# gps_transmitter_featherwing_v1_0.net
KiCad netlist of a schematic drawn in EAGLE
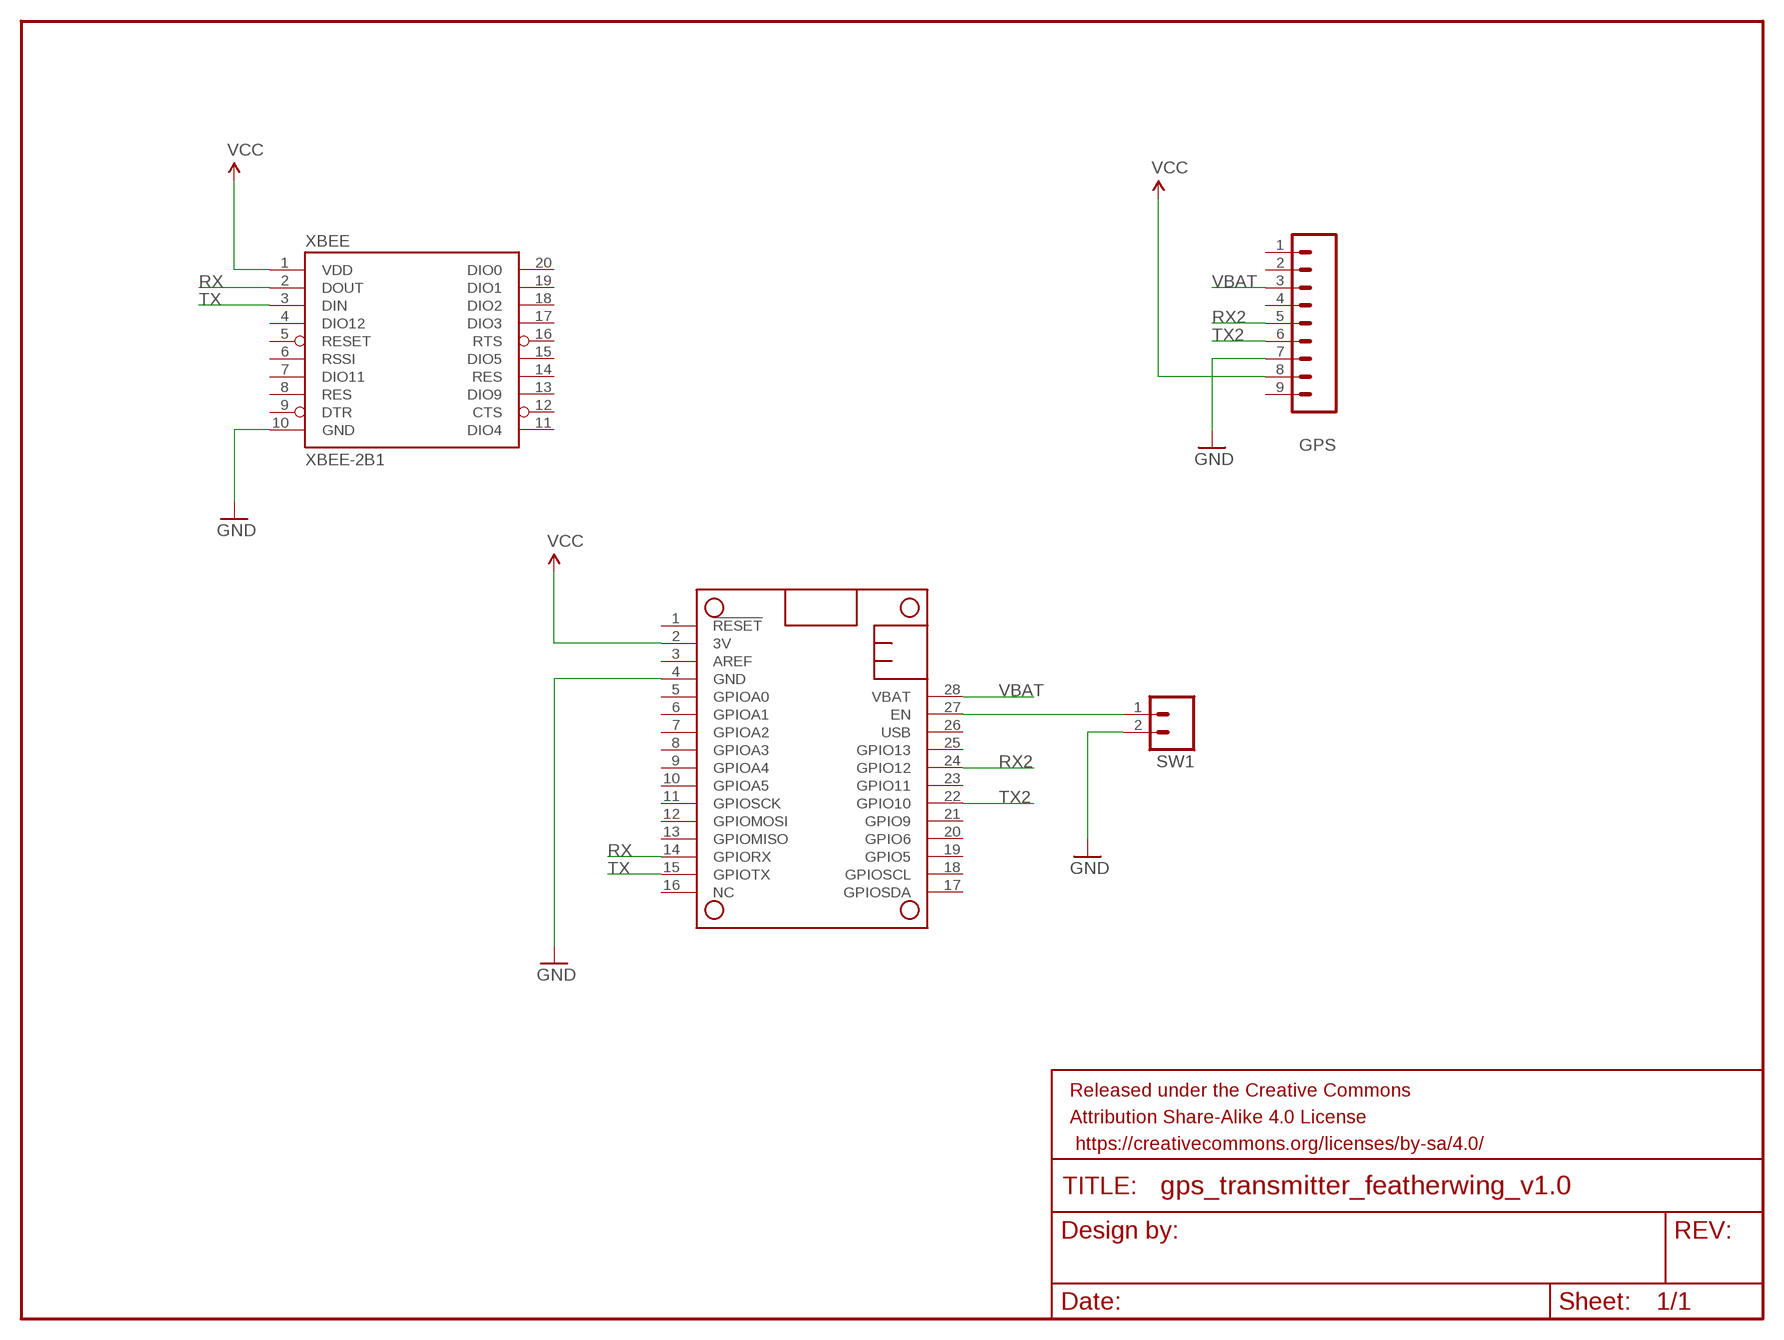
[diagram p0: schematic, sheet 1]

(export (version "E")
  (design (tool "Eeschema 10.0.6"))
  (components
    (comp (ref "FRAME1")
      (value "FRAME-LETTER")
      (footprint "eagle-import:CREATIVE_COMMONS")
      (libsource (lib "eagle-import") (part "FRAME-LETTER"))
    )
    (comp (ref "GPS")
      (value "M09")
      (footprint "eagle-import:1X09")
      (libsource (lib "eagle-import") (part "M09"))
    )
    (comp (ref "MS1")
      (value "FEATHERWING_NODIM")
      (footprint "eagle-import:FEATHERWING_DIM")
      (libsource (lib "eagle-import") (part "FEATHERWING_NODIM"))
    )
    (comp (ref "SW1")
      (value "M023.5MM")
      (footprint "eagle-import:SCREWTERMINAL-3.5MM-2")
      (libsource (lib "eagle-import") (part "M023.5MM"))
    )
    (comp (ref "XBEE")
      (value "XBEE-2B1")
      (footprint "eagle-import:XBEE-1")
      (libsource (lib "eagle-import") (part "XBEE-2B1"))
    )
  )
  (nets
    (net (code "1") (name "/RX") (class "Default")
      (node (ref "MS1") (pin "14") (pinfunction "GPIORX_14") (pintype "bidirectional"))
      (node (ref "XBEE") (pin "2") (pinfunction "DOUT_2") (pintype "output"))
    )
    (net (code "2") (name "/RX2") (class "Default")
      (node (ref "GPS") (pin "5") (pinfunction "5_5") (pintype "passive"))
      (node (ref "MS1") (pin "24") (pinfunction "GPIO12_24") (pintype "bidirectional"))
    )
    (net (code "3") (name "/TX") (class "Default")
      (node (ref "MS1") (pin "15") (pinfunction "GPIOTX_15") (pintype "bidirectional"))
      (node (ref "XBEE") (pin "3") (pinfunction "DIN_3") (pintype "input"))
    )
    (net (code "4") (name "/TX2") (class "Default")
      (node (ref "GPS") (pin "6") (pinfunction "6_6") (pintype "passive"))
      (node (ref "MS1") (pin "22") (pinfunction "GPIO10_22") (pintype "bidirectional"))
    )
    (net (code "5") (name "/USB") (class "Default")
      (node (ref "MS1") (pin "26") (pinfunction "USB_26") (pintype "power_in"))
    )
    (net (code "6") (name "/VBAT") (class "Default")
      (node (ref "GPS") (pin "3") (pinfunction "3_3") (pintype "passive"))
      (node (ref "MS1") (pin "28") (pinfunction "VBAT_28") (pintype "power_in"))
    )
    (net (code "7") (name "GND") (class "Default")
      (node (ref "GPS") (pin "7") (pinfunction "7_7") (pintype "passive"))
      (node (ref "MS1") (pin "4") (pinfunction "GND_4") (pintype "power_in"))
      (node (ref "SW1") (pin "2") (pinfunction "2_2") (pintype "passive"))
      (node (ref "XBEE") (pin "10") (pinfunction "GND_10") (pintype "power_in"))
    )
    (net (code "8") (name "Net-(MS1-EN)") (class "Default")
      (node (ref "MS1") (pin "27") (pinfunction "EN_27") (pintype "passive"))
      (node (ref "SW1") (pin "1") (pinfunction "1_1") (pintype "passive"))
    )
    (net (code "9") (name "VCC") (class "Default")
      (node (ref "GPS") (pin "8") (pinfunction "8_8") (pintype "passive"))
      (node (ref "MS1") (pin "2") (pinfunction "3V_2") (pintype "power_in"))
      (node (ref "XBEE") (pin "1") (pinfunction "VDD_1") (pintype "power_in"))
    )
    (net (code "10") (name "unconnected-(GPS-Pad1)") (class "Default")
      (node (ref "GPS") (pin "1") (pinfunction "1_1") (pintype "passive"))
    )
    (net (code "11") (name "unconnected-(GPS-Pad2)") (class "Default")
      (node (ref "GPS") (pin "2") (pinfunction "2_2") (pintype "passive"))
    )
    (net (code "12") (name "unconnected-(GPS-Pad4)") (class "Default")
      (node (ref "GPS") (pin "4") (pinfunction "4_4") (pintype "passive"))
    )
    (net (code "13") (name "unconnected-(GPS-Pad9)") (class "Default")
      (node (ref "GPS") (pin "9") (pinfunction "9_9") (pintype "passive"))
    )
    (net (code "14") (name "unconnected-(MS1-AREF-Pad3)") (class "Default")
      (node (ref "MS1") (pin "3") (pinfunction "AREF_3") (pintype "passive"))
    )
    (net (code "15") (name "unconnected-(MS1-GPIO5-Pad19)") (class "Default")
      (node (ref "MS1") (pin "19") (pinfunction "GPIO5_19") (pintype "bidirectional"))
    )
    (net (code "16") (name "unconnected-(MS1-GPIO6-Pad20)") (class "Default")
      (node (ref "MS1") (pin "20") (pinfunction "GPIO6_20") (pintype "bidirectional"))
    )
    (net (code "17") (name "unconnected-(MS1-GPIO9-Pad21)") (class "Default")
      (node (ref "MS1") (pin "21") (pinfunction "GPIO9_21") (pintype "bidirectional"))
    )
    (net (code "18") (name "unconnected-(MS1-GPIO11-Pad23)") (class "Default")
      (node (ref "MS1") (pin "23") (pinfunction "GPIO11_23") (pintype "bidirectional"))
    )
    (net (code "19") (name "unconnected-(MS1-GPIO13-Pad25)") (class "Default")
      (node (ref "MS1") (pin "25") (pinfunction "GPIO13_25") (pintype "bidirectional"))
    )
    (net (code "20") (name "unconnected-(MS1-GPIOA0-Pad5)") (class "Default")
      (node (ref "MS1") (pin "5") (pinfunction "GPIOA0_5") (pintype "bidirectional"))
    )
    (net (code "21") (name "unconnected-(MS1-GPIOA1-Pad6)") (class "Default")
      (node (ref "MS1") (pin "6") (pinfunction "GPIOA1_6") (pintype "bidirectional"))
    )
    (net (code "22") (name "unconnected-(MS1-GPIOA2-Pad7)") (class "Default")
      (node (ref "MS1") (pin "7") (pinfunction "GPIOA2_7") (pintype "bidirectional"))
    )
    (net (code "23") (name "unconnected-(MS1-GPIOA3-Pad8)") (class "Default")
      (node (ref "MS1") (pin "8") (pinfunction "GPIOA3_8") (pintype "bidirectional"))
    )
    (net (code "24") (name "unconnected-(MS1-GPIOA4-Pad9)") (class "Default")
      (node (ref "MS1") (pin "9") (pinfunction "GPIOA4_9") (pintype "bidirectional"))
    )
    (net (code "25") (name "unconnected-(MS1-GPIOA5-Pad10)") (class "Default")
      (node (ref "MS1") (pin "10") (pinfunction "GPIOA5_10") (pintype "bidirectional"))
    )
    (net (code "26") (name "unconnected-(MS1-GPIOMISO-Pad13)") (class "Default")
      (node (ref "MS1") (pin "13") (pinfunction "GPIOMISO_13") (pintype "bidirectional"))
    )
    (net (code "27") (name "unconnected-(MS1-GPIOMOSI-Pad12)") (class "Default")
      (node (ref "MS1") (pin "12") (pinfunction "GPIOMOSI_12") (pintype "bidirectional"))
    )
    (net (code "28") (name "unconnected-(MS1-GPIOSCK-Pad11)") (class "Default")
      (node (ref "MS1") (pin "11") (pinfunction "GPIOSCK_11") (pintype "bidirectional"))
    )
    (net (code "29") (name "unconnected-(MS1-GPIOSCL-Pad18)") (class "Default")
      (node (ref "MS1") (pin "18") (pinfunction "GPIOSCL_18") (pintype "bidirectional"))
    )
    (net (code "30") (name "unconnected-(MS1-GPIOSDA-Pad17)") (class "Default")
      (node (ref "MS1") (pin "17") (pinfunction "GPIOSDA_17") (pintype "bidirectional"))
    )
    (net (code "31") (name "unconnected-(MS1-NC-Pad16)") (class "Default")
      (node (ref "MS1") (pin "16") (pinfunction "NC_16") (pintype "passive"))
    )
    (net (code "32") (name "unconnected-(MS1-~{RESET}-Pad1)") (class "Default")
      (node (ref "MS1") (pin "1") (pinfunction "~{RESET}_1") (pintype "input"))
    )
    (net (code "33") (name "unconnected-(XBEE-CTS-Pad12)") (class "Default")
      (node (ref "XBEE") (pin "12") (pinfunction "CTS_12") (pintype "output"))
    )
    (net (code "34") (name "unconnected-(XBEE-DIO0-Pad20)") (class "Default")
      (node (ref "XBEE") (pin "20") (pinfunction "DIO0_20") (pintype "bidirectional"))
    )
    (net (code "35") (name "unconnected-(XBEE-DIO1-Pad19)") (class "Default")
      (node (ref "XBEE") (pin "19") (pinfunction "DIO1_19") (pintype "bidirectional"))
    )
    (net (code "36") (name "unconnected-(XBEE-DIO2-Pad18)") (class "Default")
      (node (ref "XBEE") (pin "18") (pinfunction "DIO2_18") (pintype "bidirectional"))
    )
    (net (code "37") (name "unconnected-(XBEE-DIO3-Pad17)") (class "Default")
      (node (ref "XBEE") (pin "17") (pinfunction "DIO3_17") (pintype "bidirectional"))
    )
    (net (code "38") (name "unconnected-(XBEE-DIO4-Pad11)") (class "Default")
      (node (ref "XBEE") (pin "11") (pinfunction "DIO4_11") (pintype "bidirectional"))
    )
    (net (code "39") (name "unconnected-(XBEE-DIO5-Pad15)") (class "Default")
      (node (ref "XBEE") (pin "15") (pinfunction "DIO5_15") (pintype "bidirectional"))
    )
    (net (code "40") (name "unconnected-(XBEE-DIO9-Pad13)") (class "Default")
      (node (ref "XBEE") (pin "13") (pinfunction "DIO9_13") (pintype "bidirectional"))
    )
    (net (code "41") (name "unconnected-(XBEE-DIO11-Pad7)") (class "Default")
      (node (ref "XBEE") (pin "7") (pinfunction "DIO11_7") (pintype "bidirectional"))
    )
    (net (code "42") (name "unconnected-(XBEE-DIO12-Pad4)") (class "Default")
      (node (ref "XBEE") (pin "4") (pinfunction "DIO12_4") (pintype "bidirectional"))
    )
    (net (code "43") (name "unconnected-(XBEE-DTR-Pad9)") (class "Default")
      (node (ref "XBEE") (pin "9") (pinfunction "DTR_9") (pintype "bidirectional"))
    )
    (net (code "44") (name "unconnected-(XBEE-RES-Pad8)") (class "Default")
      (node (ref "XBEE") (pin "8") (pinfunction "RES_8") (pintype "bidirectional"))
    )
    (net (code "45") (name "unconnected-(XBEE-RES-Pad14)") (class "Default")
      (node (ref "XBEE") (pin "14") (pinfunction "RES_14") (pintype "bidirectional"))
    )
    (net (code "46") (name "unconnected-(XBEE-RESET-Pad5)") (class "Default")
      (node (ref "XBEE") (pin "5") (pinfunction "RESET_5") (pintype "input"))
    )
    (net (code "47") (name "unconnected-(XBEE-RSSI-Pad6)") (class "Default")
      (node (ref "XBEE") (pin "6") (pinfunction "RSSI_6") (pintype "bidirectional"))
    )
    (net (code "48") (name "unconnected-(XBEE-RTS-Pad16)") (class "Default")
      (node (ref "XBEE") (pin "16") (pinfunction "RTS_16") (pintype "input"))
    )
  )
)
